# 7-InputSelect.net
KiCad netlist of a schematic drawn in EAGLE
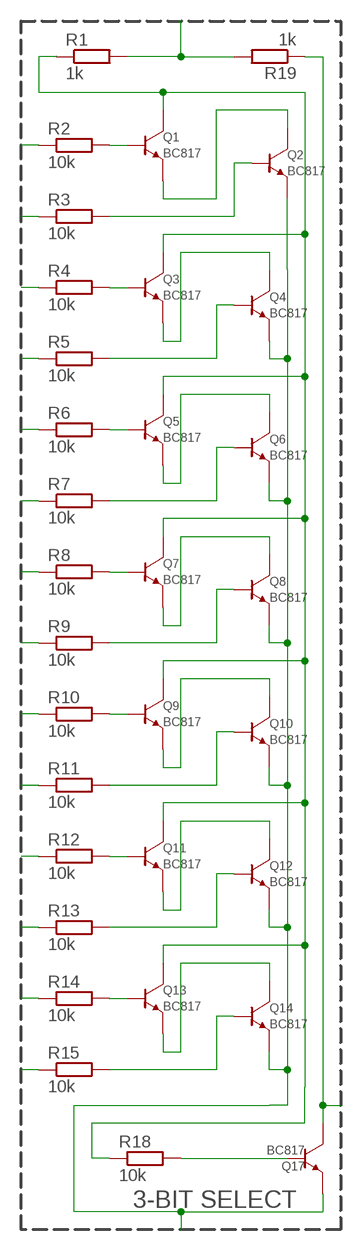
[diagram p0: schematic, sheet 1]

(export (version "E")
  (design (tool "Eeschema 10.0.6"))
  (components
    (comp (ref "Q1")
      (value "BC817")
      (footprint "eagle-import:SOT23")
      (libsource (lib "eagle-import") (part "TRANSISTOR-NPN-GENERIC-SOT23-BECDEFAULT"))
    )
    (comp (ref "Q2")
      (value "BC817")
      (footprint "eagle-import:SOT23")
      (libsource (lib "eagle-import") (part "TRANSISTOR-NPN-GENERIC-SOT23-BECDEFAULT"))
    )
    (comp (ref "Q3")
      (value "BC817")
      (footprint "eagle-import:SOT23")
      (libsource (lib "eagle-import") (part "TRANSISTOR-NPN-GENERIC-SOT23-BECDEFAULT"))
    )
    (comp (ref "Q4")
      (value "BC817")
      (footprint "eagle-import:SOT23")
      (libsource (lib "eagle-import") (part "TRANSISTOR-NPN-GENERIC-SOT23-BECDEFAULT"))
    )
    (comp (ref "Q5")
      (value "BC817")
      (footprint "eagle-import:SOT23")
      (libsource (lib "eagle-import") (part "TRANSISTOR-NPN-GENERIC-SOT23-BECDEFAULT"))
    )
    (comp (ref "Q6")
      (value "BC817")
      (footprint "eagle-import:SOT23")
      (libsource (lib "eagle-import") (part "TRANSISTOR-NPN-GENERIC-SOT23-BECDEFAULT"))
    )
    (comp (ref "Q7")
      (value "BC817")
      (footprint "eagle-import:SOT23")
      (libsource (lib "eagle-import") (part "TRANSISTOR-NPN-GENERIC-SOT23-BECDEFAULT"))
    )
    (comp (ref "Q8")
      (value "BC817")
      (footprint "eagle-import:SOT23")
      (libsource (lib "eagle-import") (part "TRANSISTOR-NPN-GENERIC-SOT23-BECDEFAULT"))
    )
    (comp (ref "Q9")
      (value "BC817")
      (footprint "eagle-import:SOT23")
      (libsource (lib "eagle-import") (part "TRANSISTOR-NPN-GENERIC-SOT23-BECDEFAULT"))
    )
    (comp (ref "Q10")
      (value "BC817")
      (footprint "eagle-import:SOT23")
      (libsource (lib "eagle-import") (part "TRANSISTOR-NPN-GENERIC-SOT23-BECDEFAULT"))
    )
    (comp (ref "Q11")
      (value "BC817")
      (footprint "eagle-import:SOT23")
      (libsource (lib "eagle-import") (part "TRANSISTOR-NPN-GENERIC-SOT23-BECDEFAULT"))
    )
    (comp (ref "Q12")
      (value "BC817")
      (footprint "eagle-import:SOT23")
      (libsource (lib "eagle-import") (part "TRANSISTOR-NPN-GENERIC-SOT23-BECDEFAULT"))
    )
    (comp (ref "Q13")
      (value "BC817")
      (footprint "eagle-import:SOT23")
      (libsource (lib "eagle-import") (part "TRANSISTOR-NPN-GENERIC-SOT23-BECDEFAULT"))
    )
    (comp (ref "Q14")
      (value "BC817")
      (footprint "eagle-import:SOT23")
      (libsource (lib "eagle-import") (part "TRANSISTOR-NPN-GENERIC-SOT23-BECDEFAULT"))
    )
    (comp (ref "Q17")
      (value "BC817")
      (footprint "eagle-import:SOT23")
      (libsource (lib "eagle-import") (part "TRANSISTOR-NPN-GENERIC-SOT23-BECDEFAULT"))
    )
    (comp (ref "R1")
      (value "1k")
      (footprint "eagle-import:R0603")
      (libsource (lib "eagle-import") (part "R-EU_R0603"))
    )
    (comp (ref "R2")
      (value "10k")
      (footprint "eagle-import:R0603")
      (libsource (lib "eagle-import") (part "R-EU_R0603"))
    )
    (comp (ref "R3")
      (value "10k")
      (footprint "eagle-import:R0603")
      (libsource (lib "eagle-import") (part "R-EU_R0603"))
    )
    (comp (ref "R4")
      (value "10k")
      (footprint "eagle-import:R0603")
      (libsource (lib "eagle-import") (part "R-EU_R0603"))
    )
    (comp (ref "R5")
      (value "10k")
      (footprint "eagle-import:R0603")
      (libsource (lib "eagle-import") (part "R-EU_R0603"))
    )
    (comp (ref "R6")
      (value "10k")
      (footprint "eagle-import:R0603")
      (libsource (lib "eagle-import") (part "R-EU_R0603"))
    )
    (comp (ref "R7")
      (value "10k")
      (footprint "eagle-import:R0603")
      (libsource (lib "eagle-import") (part "R-EU_R0603"))
    )
    (comp (ref "R8")
      (value "10k")
      (footprint "eagle-import:R0603")
      (libsource (lib "eagle-import") (part "R-EU_R0603"))
    )
    (comp (ref "R9")
      (value "10k")
      (footprint "eagle-import:R0603")
      (libsource (lib "eagle-import") (part "R-EU_R0603"))
    )
    (comp (ref "R10")
      (value "10k")
      (footprint "eagle-import:R0603")
      (libsource (lib "eagle-import") (part "R-EU_R0603"))
    )
    (comp (ref "R11")
      (value "10k")
      (footprint "eagle-import:R0603")
      (libsource (lib "eagle-import") (part "R-EU_R0603"))
    )
    (comp (ref "R12")
      (value "10k")
      (footprint "eagle-import:R0603")
      (libsource (lib "eagle-import") (part "R-EU_R0603"))
    )
    (comp (ref "R13")
      (value "10k")
      (footprint "eagle-import:R0603")
      (libsource (lib "eagle-import") (part "R-EU_R0603"))
    )
    (comp (ref "R14")
      (value "10k")
      (footprint "eagle-import:R0603")
      (libsource (lib "eagle-import") (part "R-EU_R0603"))
    )
    (comp (ref "R15")
      (value "10k")
      (footprint "eagle-import:R0603")
      (libsource (lib "eagle-import") (part "R-EU_R0603"))
    )
    (comp (ref "R18")
      (value "10k")
      (footprint "eagle-import:R0603")
      (libsource (lib "eagle-import") (part "R-EU_R0603"))
    )
    (comp (ref "R19")
      (value "1k")
      (footprint "eagle-import:R0603")
      (libsource (lib "eagle-import") (part "R-EU_R0603"))
    )
  )
  (nets
    (net (code "1") (name "Net-(Q1-BASE)") (class "Default")
      (node (ref "Q1") (pin "P$1") (pinfunction "BASE_P$1") (pintype "bidirectional"))
      (node (ref "R2") (pin "2") (pinfunction "2_2") (pintype "passive"))
    )
    (net (code "2") (name "Net-(Q1-COLLECTOR)") (class "Default")
      (node (ref "Q1") (pin "P$3") (pinfunction "COLLECTOR_P$3") (pintype "bidirectional"))
      (node (ref "Q11") (pin "P$3") (pinfunction "COLLECTOR_P$3") (pintype "bidirectional"))
      (node (ref "Q13") (pin "P$3") (pinfunction "COLLECTOR_P$3") (pintype "bidirectional"))
      (node (ref "Q3") (pin "P$3") (pinfunction "COLLECTOR_P$3") (pintype "bidirectional"))
      (node (ref "Q5") (pin "P$3") (pinfunction "COLLECTOR_P$3") (pintype "bidirectional"))
      (node (ref "Q7") (pin "P$3") (pinfunction "COLLECTOR_P$3") (pintype "bidirectional"))
      (node (ref "Q9") (pin "P$3") (pinfunction "COLLECTOR_P$3") (pintype "bidirectional"))
      (node (ref "R1") (pin "1") (pinfunction "1_1") (pintype "passive"))
      (node (ref "R18") (pin "1") (pinfunction "1_1") (pintype "passive"))
    )
    (net (code "3") (name "Net-(Q1-EMITTER)") (class "Default")
      (node (ref "Q1") (pin "P$2") (pinfunction "EMITTER_P$2") (pintype "bidirectional"))
      (node (ref "Q2") (pin "P$3") (pinfunction "COLLECTOR_P$3") (pintype "bidirectional"))
    )
    (net (code "4") (name "Net-(Q2-BASE)") (class "Default")
      (node (ref "Q2") (pin "P$1") (pinfunction "BASE_P$1") (pintype "bidirectional"))
      (node (ref "R3") (pin "2") (pinfunction "2_2") (pintype "passive"))
    )
    (net (code "5") (name "Net-(Q3-BASE)") (class "Default")
      (node (ref "Q3") (pin "P$1") (pinfunction "BASE_P$1") (pintype "bidirectional"))
      (node (ref "R4") (pin "2") (pinfunction "2_2") (pintype "passive"))
    )
    (net (code "6") (name "Net-(Q3-EMITTER)") (class "Default")
      (node (ref "Q3") (pin "P$2") (pinfunction "EMITTER_P$2") (pintype "bidirectional"))
      (node (ref "Q4") (pin "P$3") (pinfunction "COLLECTOR_P$3") (pintype "bidirectional"))
    )
    (net (code "7") (name "Net-(Q4-BASE)") (class "Default")
      (node (ref "Q4") (pin "P$1") (pinfunction "BASE_P$1") (pintype "bidirectional"))
      (node (ref "R5") (pin "2") (pinfunction "2_2") (pintype "passive"))
    )
    (net (code "8") (name "Net-(Q5-BASE)") (class "Default")
      (node (ref "Q5") (pin "P$1") (pinfunction "BASE_P$1") (pintype "bidirectional"))
      (node (ref "R6") (pin "2") (pinfunction "2_2") (pintype "passive"))
    )
    (net (code "9") (name "Net-(Q5-EMITTER)") (class "Default")
      (node (ref "Q5") (pin "P$2") (pinfunction "EMITTER_P$2") (pintype "bidirectional"))
      (node (ref "Q6") (pin "P$3") (pinfunction "COLLECTOR_P$3") (pintype "bidirectional"))
    )
    (net (code "10") (name "Net-(Q6-BASE)") (class "Default")
      (node (ref "Q6") (pin "P$1") (pinfunction "BASE_P$1") (pintype "bidirectional"))
      (node (ref "R7") (pin "2") (pinfunction "2_2") (pintype "passive"))
    )
    (net (code "11") (name "Net-(Q7-BASE)") (class "Default")
      (node (ref "Q7") (pin "P$1") (pinfunction "BASE_P$1") (pintype "bidirectional"))
      (node (ref "R8") (pin "2") (pinfunction "2_2") (pintype "passive"))
    )
    (net (code "12") (name "Net-(Q7-EMITTER)") (class "Default")
      (node (ref "Q7") (pin "P$2") (pinfunction "EMITTER_P$2") (pintype "bidirectional"))
      (node (ref "Q8") (pin "P$3") (pinfunction "COLLECTOR_P$3") (pintype "bidirectional"))
    )
    (net (code "13") (name "Net-(Q8-BASE)") (class "Default")
      (node (ref "Q8") (pin "P$1") (pinfunction "BASE_P$1") (pintype "bidirectional"))
      (node (ref "R9") (pin "2") (pinfunction "2_2") (pintype "passive"))
    )
    (net (code "14") (name "Net-(Q9-BASE)") (class "Default")
      (node (ref "Q9") (pin "P$1") (pinfunction "BASE_P$1") (pintype "bidirectional"))
      (node (ref "R10") (pin "2") (pinfunction "2_2") (pintype "passive"))
    )
    (net (code "15") (name "Net-(Q10-BASE)") (class "Default")
      (node (ref "Q10") (pin "P$1") (pinfunction "BASE_P$1") (pintype "bidirectional"))
      (node (ref "R11") (pin "2") (pinfunction "2_2") (pintype "passive"))
    )
    (net (code "16") (name "Net-(Q10-COLLECTOR)") (class "Default")
      (node (ref "Q10") (pin "P$3") (pinfunction "COLLECTOR_P$3") (pintype "bidirectional"))
      (node (ref "Q9") (pin "P$2") (pinfunction "EMITTER_P$2") (pintype "bidirectional"))
    )
    (net (code "17") (name "Net-(Q10-EMITTER)") (class "Default")
      (node (ref "Q10") (pin "P$2") (pinfunction "EMITTER_P$2") (pintype "bidirectional"))
      (node (ref "Q12") (pin "P$2") (pinfunction "EMITTER_P$2") (pintype "bidirectional"))
      (node (ref "Q14") (pin "P$2") (pinfunction "EMITTER_P$2") (pintype "bidirectional"))
      (node (ref "Q17") (pin "P$2") (pinfunction "EMITTER_P$2") (pintype "bidirectional"))
      (node (ref "Q2") (pin "P$2") (pinfunction "EMITTER_P$2") (pintype "bidirectional"))
      (node (ref "Q4") (pin "P$2") (pinfunction "EMITTER_P$2") (pintype "bidirectional"))
      (node (ref "Q6") (pin "P$2") (pinfunction "EMITTER_P$2") (pintype "bidirectional"))
      (node (ref "Q8") (pin "P$2") (pinfunction "EMITTER_P$2") (pintype "bidirectional"))
    )
    (net (code "18") (name "Net-(Q11-BASE)") (class "Default")
      (node (ref "Q11") (pin "P$1") (pinfunction "BASE_P$1") (pintype "bidirectional"))
      (node (ref "R12") (pin "2") (pinfunction "2_2") (pintype "passive"))
    )
    (net (code "19") (name "Net-(Q11-EMITTER)") (class "Default")
      (node (ref "Q11") (pin "P$2") (pinfunction "EMITTER_P$2") (pintype "bidirectional"))
      (node (ref "Q12") (pin "P$3") (pinfunction "COLLECTOR_P$3") (pintype "bidirectional"))
    )
    (net (code "20") (name "Net-(Q12-BASE)") (class "Default")
      (node (ref "Q12") (pin "P$1") (pinfunction "BASE_P$1") (pintype "bidirectional"))
      (node (ref "R13") (pin "2") (pinfunction "2_2") (pintype "passive"))
    )
    (net (code "21") (name "Net-(Q13-BASE)") (class "Default")
      (node (ref "Q13") (pin "P$1") (pinfunction "BASE_P$1") (pintype "bidirectional"))
      (node (ref "R14") (pin "2") (pinfunction "2_2") (pintype "passive"))
    )
    (net (code "22") (name "Net-(Q13-EMITTER)") (class "Default")
      (node (ref "Q13") (pin "P$2") (pinfunction "EMITTER_P$2") (pintype "bidirectional"))
      (node (ref "Q14") (pin "P$3") (pinfunction "COLLECTOR_P$3") (pintype "bidirectional"))
    )
    (net (code "23") (name "Net-(Q14-BASE)") (class "Default")
      (node (ref "Q14") (pin "P$1") (pinfunction "BASE_P$1") (pintype "bidirectional"))
      (node (ref "R15") (pin "2") (pinfunction "2_2") (pintype "passive"))
    )
    (net (code "24") (name "Net-(Q17-BASE)") (class "Default")
      (node (ref "Q17") (pin "P$1") (pinfunction "BASE_P$1") (pintype "bidirectional"))
      (node (ref "R18") (pin "2") (pinfunction "2_2") (pintype "passive"))
    )
    (net (code "25") (name "Net-(Q17-COLLECTOR)") (class "Default")
      (node (ref "Q17") (pin "P$3") (pinfunction "COLLECTOR_P$3") (pintype "bidirectional"))
      (node (ref "R19") (pin "1") (pinfunction "1_1") (pintype "passive"))
    )
    (net (code "26") (name "Net-(R1-Pad2)") (class "Default")
      (node (ref "R1") (pin "2") (pinfunction "2_2") (pintype "passive"))
      (node (ref "R19") (pin "2") (pinfunction "2_2") (pintype "passive"))
    )
    (net (code "27") (name "unconnected-(R2-Pad1)") (class "Default")
      (node (ref "R2") (pin "1") (pinfunction "1_1") (pintype "passive"))
    )
    (net (code "28") (name "unconnected-(R3-Pad1)") (class "Default")
      (node (ref "R3") (pin "1") (pinfunction "1_1") (pintype "passive"))
    )
    (net (code "29") (name "unconnected-(R4-Pad1)") (class "Default")
      (node (ref "R4") (pin "1") (pinfunction "1_1") (pintype "passive"))
    )
    (net (code "30") (name "unconnected-(R5-Pad1)") (class "Default")
      (node (ref "R5") (pin "1") (pinfunction "1_1") (pintype "passive"))
    )
    (net (code "31") (name "unconnected-(R6-Pad1)") (class "Default")
      (node (ref "R6") (pin "1") (pinfunction "1_1") (pintype "passive"))
    )
    (net (code "32") (name "unconnected-(R7-Pad1)") (class "Default")
      (node (ref "R7") (pin "1") (pinfunction "1_1") (pintype "passive"))
    )
    (net (code "33") (name "unconnected-(R8-Pad1)") (class "Default")
      (node (ref "R8") (pin "1") (pinfunction "1_1") (pintype "passive"))
    )
    (net (code "34") (name "unconnected-(R9-Pad1)") (class "Default")
      (node (ref "R9") (pin "1") (pinfunction "1_1") (pintype "passive"))
    )
    (net (code "35") (name "unconnected-(R10-Pad1)") (class "Default")
      (node (ref "R10") (pin "1") (pinfunction "1_1") (pintype "passive"))
    )
    (net (code "36") (name "unconnected-(R11-Pad1)") (class "Default")
      (node (ref "R11") (pin "1") (pinfunction "1_1") (pintype "passive"))
    )
    (net (code "37") (name "unconnected-(R12-Pad1)") (class "Default")
      (node (ref "R12") (pin "1") (pinfunction "1_1") (pintype "passive"))
    )
    (net (code "38") (name "unconnected-(R13-Pad1)") (class "Default")
      (node (ref "R13") (pin "1") (pinfunction "1_1") (pintype "passive"))
    )
    (net (code "39") (name "unconnected-(R14-Pad1)") (class "Default")
      (node (ref "R14") (pin "1") (pinfunction "1_1") (pintype "passive"))
    )
    (net (code "40") (name "unconnected-(R15-Pad1)") (class "Default")
      (node (ref "R15") (pin "1") (pinfunction "1_1") (pintype "passive"))
    )
  )
)
